# Task0301.net
KiCad netlist of a schematic drawn in Altium Designer
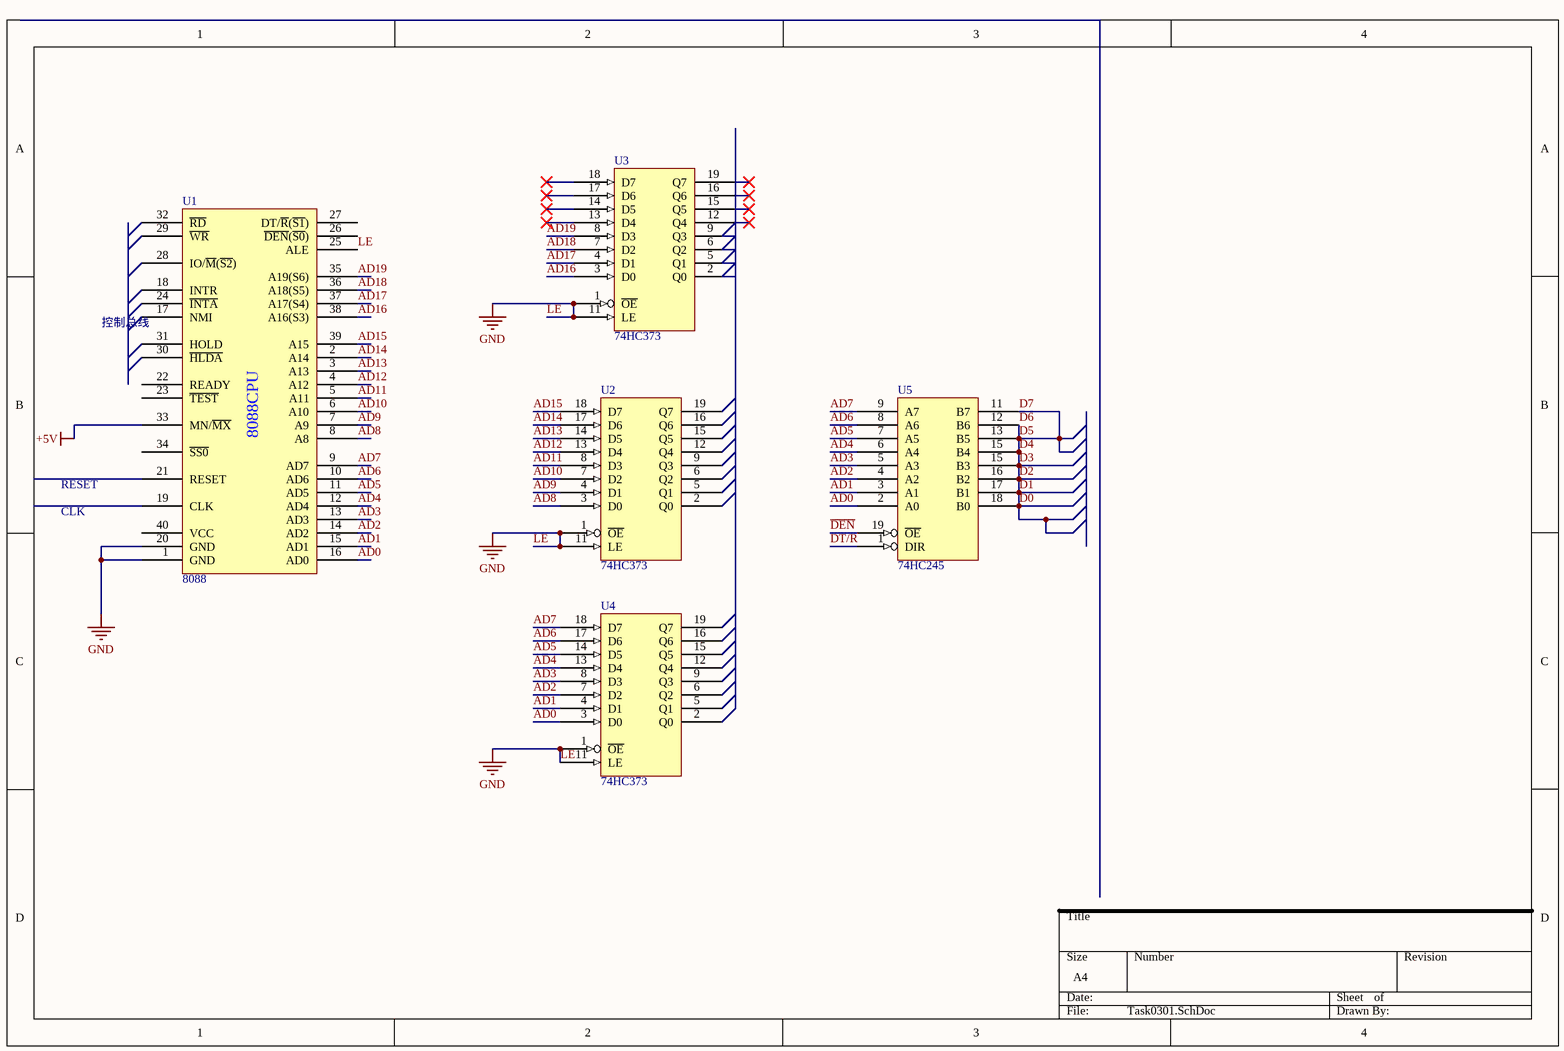
[diagram p0: Task0301.SchDoc]

(export (version "E")
  (design (tool "Eeschema 10.0.6"))
  (components
    (comp (ref "U1") (value "8088") (libsource (lib "8088ThreeBuses") (part "8088")))
    (comp (ref "U2") (value "74HC373") (libsource (lib "8088ThreeBuses") (part "74HC373")))
    (comp (ref "U3") (value "74HC373") (libsource (lib "8088ThreeBuses") (part "74HC373")))
    (comp (ref "U4") (value "74HC373") (libsource (lib "8088ThreeBuses") (part "74HC373")))
    (comp (ref "U5") (value "74HC245") (libsource (lib "8088ThreeBuses") (part "74HC245")))
  )
  (nets
    (net (code "1") (name "+5V") (class "Default")
      (node (ref "U1") (pin "33") (pinfunction "MN/~{MX}_33") (pintype "passive"))
    )
    (net (code "2") (name "/AD0") (class "Default")
      (node (ref "U1") (pin "16") (pinfunction "AD0_16") (pintype "passive"))
      (node (ref "U4") (pin "3") (pinfunction "D0_3") (pintype "input"))
      (node (ref "U5") (pin "2") (pinfunction "A0_2") (pintype "passive"))
    )
    (net (code "3") (name "/AD1") (class "Default")
      (node (ref "U1") (pin "15") (pinfunction "AD1_15") (pintype "passive"))
      (node (ref "U4") (pin "4") (pinfunction "D1_4") (pintype "input"))
      (node (ref "U5") (pin "3") (pinfunction "A1_3") (pintype "passive"))
    )
    (net (code "4") (name "/AD2") (class "Default")
      (node (ref "U1") (pin "14") (pinfunction "AD2_14") (pintype "passive"))
      (node (ref "U4") (pin "7") (pinfunction "D2_7") (pintype "input"))
      (node (ref "U5") (pin "4") (pinfunction "A2_4") (pintype "passive"))
    )
    (net (code "5") (name "/AD3") (class "Default")
      (node (ref "U1") (pin "13") (pinfunction "AD3_13") (pintype "passive"))
      (node (ref "U4") (pin "8") (pinfunction "D3_8") (pintype "input"))
      (node (ref "U5") (pin "5") (pinfunction "A3_5") (pintype "passive"))
    )
    (net (code "6") (name "/AD4") (class "Default")
      (node (ref "U1") (pin "12") (pinfunction "AD4_12") (pintype "passive"))
      (node (ref "U4") (pin "13") (pinfunction "D4_13") (pintype "input"))
      (node (ref "U5") (pin "6") (pinfunction "A4_6") (pintype "passive"))
    )
    (net (code "7") (name "/AD5") (class "Default")
      (node (ref "U1") (pin "11") (pinfunction "AD5_11") (pintype "passive"))
      (node (ref "U4") (pin "14") (pinfunction "D5_14") (pintype "input"))
      (node (ref "U5") (pin "7") (pinfunction "A5_7") (pintype "passive"))
    )
    (net (code "8") (name "/AD6") (class "Default")
      (node (ref "U1") (pin "10") (pinfunction "AD6_10") (pintype "passive"))
      (node (ref "U4") (pin "17") (pinfunction "D6_17") (pintype "input"))
      (node (ref "U5") (pin "8") (pinfunction "A6_8") (pintype "passive"))
    )
    (net (code "9") (name "/AD7") (class "Default")
      (node (ref "U1") (pin "9") (pinfunction "AD7_9") (pintype "passive"))
      (node (ref "U4") (pin "18") (pinfunction "D7_18") (pintype "input"))
      (node (ref "U5") (pin "9") (pinfunction "A7_9") (pintype "passive"))
    )
    (net (code "10") (name "/AD8") (class "Default")
      (node (ref "U1") (pin "8") (pinfunction "A8_8") (pintype "passive"))
      (node (ref "U2") (pin "3") (pinfunction "D0_3") (pintype "input"))
    )
    (net (code "11") (name "/AD9") (class "Default")
      (node (ref "U1") (pin "7") (pinfunction "A9_7") (pintype "passive"))
      (node (ref "U2") (pin "4") (pinfunction "D1_4") (pintype "input"))
    )
    (net (code "12") (name "/AD10") (class "Default")
      (node (ref "U1") (pin "6") (pinfunction "A10_6") (pintype "passive"))
      (node (ref "U2") (pin "7") (pinfunction "D2_7") (pintype "input"))
    )
    (net (code "13") (name "/AD11") (class "Default")
      (node (ref "U1") (pin "5") (pinfunction "A11_5") (pintype "passive"))
      (node (ref "U2") (pin "8") (pinfunction "D3_8") (pintype "input"))
    )
    (net (code "14") (name "/AD12") (class "Default")
      (node (ref "U1") (pin "4") (pinfunction "A12_4") (pintype "passive"))
      (node (ref "U2") (pin "13") (pinfunction "D4_13") (pintype "input"))
    )
    (net (code "15") (name "/AD13") (class "Default")
      (node (ref "U1") (pin "3") (pinfunction "A13_3") (pintype "passive"))
      (node (ref "U2") (pin "14") (pinfunction "D5_14") (pintype "input"))
    )
    (net (code "16") (name "/AD14") (class "Default")
      (node (ref "U1") (pin "2") (pinfunction "A14_2") (pintype "passive"))
      (node (ref "U2") (pin "17") (pinfunction "D6_17") (pintype "input"))
    )
    (net (code "17") (name "/AD15") (class "Default")
      (node (ref "U1") (pin "39") (pinfunction "A15_39") (pintype "passive"))
      (node (ref "U2") (pin "18") (pinfunction "D7_18") (pintype "input"))
    )
    (net (code "18") (name "/AD16") (class "Default")
      (node (ref "U1") (pin "38") (pinfunction "A16(S3)_38") (pintype "passive"))
      (node (ref "U3") (pin "3") (pinfunction "D0_3") (pintype "input"))
    )
    (net (code "19") (name "/AD17") (class "Default")
      (node (ref "U1") (pin "37") (pinfunction "A17(S4)_37") (pintype "passive"))
      (node (ref "U3") (pin "4") (pinfunction "D1_4") (pintype "input"))
    )
    (net (code "20") (name "/AD18") (class "Default")
      (node (ref "U1") (pin "36") (pinfunction "A18(S5)_36") (pintype "passive"))
      (node (ref "U3") (pin "7") (pinfunction "D2_7") (pintype "input"))
    )
    (net (code "21") (name "/AD19") (class "Default")
      (node (ref "U1") (pin "35") (pinfunction "A19(S6)_35") (pintype "passive"))
      (node (ref "U3") (pin "8") (pinfunction "D3_8") (pintype "input"))
    )
    (net (code "22") (name "/D0") (class "Default")
      (node (ref "U5") (pin "11") (pinfunction "B7_11") (pintype "tri_state"))
      (node (ref "U5") (pin "12") (pinfunction "B6_12") (pintype "tri_state"))
      (node (ref "U5") (pin "13") (pinfunction "B5_13") (pintype "tri_state"))
      (node (ref "U5") (pin "15") (pinfunction "B4_15") (pintype "tri_state"))
      (node (ref "U5") (pin "16") (pinfunction "B2_16") (pintype "tri_state"))
      (node (ref "U5") (pin "17") (pinfunction "B1_17") (pintype "tri_state"))
      (node (ref "U5") (pin "18") (pinfunction "B0_18") (pintype "tri_state"))
    )
    (net (code "23") (name "/DT{slash}~{R}") (class "Default")
      (node (ref "U5") (pin "1") (pinfunction "DIR_1") (pintype "input"))
    )
    (net (code "24") (name "/~{DEN}") (class "Default")
      (node (ref "U5") (pin "19") (pinfunction "~{OE}_19") (pintype "input"))
    )
    (net (code "25") (name "GND") (class "Default")
      (node (ref "U1") (pin "1") (pinfunction "GND_1") (pintype "passive"))
      (node (ref "U1") (pin "20") (pinfunction "GND_20") (pintype "passive"))
      (node (ref "U1") (pin "25") (pinfunction "ALE_25") (pintype "passive"))
      (node (ref "U2") (pin "1") (pinfunction "~{OE}_1") (pintype "input"))
      (node (ref "U2") (pin "11") (pinfunction "LE_11") (pintype "input"))
      (node (ref "U3") (pin "1") (pinfunction "~{OE}_1") (pintype "input"))
      (node (ref "U3") (pin "11") (pinfunction "LE_11") (pintype "input"))
      (node (ref "U4") (pin "1") (pinfunction "~{OE}_1") (pintype "input"))
      (node (ref "U4") (pin "11") (pinfunction "LE_11") (pintype "input"))
    )
    (net (code "26") (name "unconnected-(U1-CLK-Pad19)") (class "Default")
      (node (ref "U1") (pin "19") (pinfunction "CLK_19") (pintype "passive"))
    )
    (net (code "27") (name "unconnected-(U1-DT{slash}~{R}(~{S1})-Pad27)") (class "Default")
      (node (ref "U1") (pin "27") (pinfunction "DT/~{R}(~{S1})_27") (pintype "passive"))
    )
    (net (code "28") (name "unconnected-(U1-HOLD-Pad31)") (class "Default")
      (node (ref "U1") (pin "31") (pinfunction "HOLD_31") (pintype "passive"))
    )
    (net (code "29") (name "unconnected-(U1-INTR-Pad18)") (class "Default")
      (node (ref "U1") (pin "18") (pinfunction "INTR_18") (pintype "passive"))
    )
    (net (code "30") (name "unconnected-(U1-IO{slash}~{M}(~{S2})-Pad28)") (class "Default")
      (node (ref "U1") (pin "28") (pinfunction "IO/~{M}(~{S2})_28") (pintype "passive"))
    )
    (net (code "31") (name "unconnected-(U1-NMI-Pad17)") (class "Default")
      (node (ref "U1") (pin "17") (pinfunction "NMI_17") (pintype "passive"))
    )
    (net (code "32") (name "unconnected-(U1-READY-Pad22)") (class "Default")
      (node (ref "U1") (pin "22") (pinfunction "READY_22") (pintype "passive"))
    )
    (net (code "33") (name "unconnected-(U1-RESET-Pad21)") (class "Default")
      (node (ref "U1") (pin "21") (pinfunction "RESET_21") (pintype "passive"))
    )
    (net (code "34") (name "unconnected-(U1-VCC-Pad40)") (class "Default")
      (node (ref "U1") (pin "40") (pinfunction "VCC_40") (pintype "passive"))
    )
    (net (code "35") (name "unconnected-(U1-~{DEN}(~{S0})-Pad26)") (class "Default")
      (node (ref "U1") (pin "26") (pinfunction "~{DEN}(~{S0})_26") (pintype "passive"))
    )
    (net (code "36") (name "unconnected-(U1-~{HLDA}-Pad30)") (class "Default")
      (node (ref "U1") (pin "30") (pinfunction "~{HLDA}_30") (pintype "passive"))
    )
    (net (code "37") (name "unconnected-(U1-~{INTA}-Pad24)") (class "Default")
      (node (ref "U1") (pin "24") (pinfunction "~{INTA}_24") (pintype "passive"))
    )
    (net (code "38") (name "unconnected-(U1-~{RD}-Pad32)") (class "Default")
      (node (ref "U1") (pin "32") (pinfunction "~{RD}_32") (pintype "passive"))
    )
    (net (code "39") (name "unconnected-(U1-~{SS0}-Pad34)") (class "Default")
      (node (ref "U1") (pin "34") (pinfunction "~{SS0}_34") (pintype "passive"))
    )
    (net (code "40") (name "unconnected-(U1-~{TEST}-Pad23)") (class "Default")
      (node (ref "U1") (pin "23") (pinfunction "~{TEST}_23") (pintype "passive"))
    )
    (net (code "41") (name "unconnected-(U1-~{WR}-Pad29)") (class "Default")
      (node (ref "U1") (pin "29") (pinfunction "~{WR}_29") (pintype "passive"))
    )
    (net (code "42") (name "unconnected-(U2-Q0-Pad2)") (class "Default")
      (node (ref "U2") (pin "2") (pinfunction "Q0_2") (pintype "tri_state"))
    )
    (net (code "43") (name "unconnected-(U2-Q1-Pad5)") (class "Default")
      (node (ref "U2") (pin "5") (pinfunction "Q1_5") (pintype "tri_state"))
    )
    (net (code "44") (name "unconnected-(U2-Q2-Pad6)") (class "Default")
      (node (ref "U2") (pin "6") (pinfunction "Q2_6") (pintype "tri_state"))
    )
    (net (code "45") (name "unconnected-(U2-Q3-Pad9)") (class "Default")
      (node (ref "U2") (pin "9") (pinfunction "Q3_9") (pintype "tri_state"))
    )
    (net (code "46") (name "unconnected-(U2-Q4-Pad12)") (class "Default")
      (node (ref "U2") (pin "12") (pinfunction "Q4_12") (pintype "tri_state"))
    )
    (net (code "47") (name "unconnected-(U2-Q5-Pad15)") (class "Default")
      (node (ref "U2") (pin "15") (pinfunction "Q5_15") (pintype "tri_state"))
    )
    (net (code "48") (name "unconnected-(U2-Q6-Pad16)") (class "Default")
      (node (ref "U2") (pin "16") (pinfunction "Q6_16") (pintype "tri_state"))
    )
    (net (code "49") (name "unconnected-(U2-Q7-Pad19)") (class "Default")
      (node (ref "U2") (pin "19") (pinfunction "Q7_19") (pintype "tri_state"))
    )
    (net (code "50") (name "unconnected-(U3-D4-Pad13)") (class "Default")
      (node (ref "U3") (pin "13") (pinfunction "D4_13") (pintype "input+no_connect"))
    )
    (net (code "51") (name "unconnected-(U3-D5-Pad14)") (class "Default")
      (node (ref "U3") (pin "14") (pinfunction "D5_14") (pintype "input+no_connect"))
    )
    (net (code "52") (name "unconnected-(U3-D6-Pad17)") (class "Default")
      (node (ref "U3") (pin "17") (pinfunction "D6_17") (pintype "input+no_connect"))
    )
    (net (code "53") (name "unconnected-(U3-D7-Pad18)") (class "Default")
      (node (ref "U3") (pin "18") (pinfunction "D7_18") (pintype "input+no_connect"))
    )
    (net (code "54") (name "unconnected-(U3-Q0-Pad2)") (class "Default")
      (node (ref "U3") (pin "2") (pinfunction "Q0_2") (pintype "tri_state"))
    )
    (net (code "55") (name "unconnected-(U3-Q1-Pad5)") (class "Default")
      (node (ref "U3") (pin "5") (pinfunction "Q1_5") (pintype "tri_state"))
    )
    (net (code "56") (name "unconnected-(U3-Q2-Pad6)") (class "Default")
      (node (ref "U3") (pin "6") (pinfunction "Q2_6") (pintype "tri_state"))
    )
    (net (code "57") (name "unconnected-(U3-Q3-Pad9)") (class "Default")
      (node (ref "U3") (pin "9") (pinfunction "Q3_9") (pintype "tri_state"))
    )
    (net (code "58") (name "unconnected-(U3-Q4-Pad12)") (class "Default")
      (node (ref "U3") (pin "12") (pinfunction "Q4_12") (pintype "tri_state+no_connect"))
    )
    (net (code "59") (name "unconnected-(U3-Q5-Pad15)") (class "Default")
      (node (ref "U3") (pin "15") (pinfunction "Q5_15") (pintype "tri_state+no_connect"))
    )
    (net (code "60") (name "unconnected-(U3-Q6-Pad16)") (class "Default")
      (node (ref "U3") (pin "16") (pinfunction "Q6_16") (pintype "tri_state+no_connect"))
    )
    (net (code "61") (name "unconnected-(U3-Q7-Pad19)") (class "Default")
      (node (ref "U3") (pin "19") (pinfunction "Q7_19") (pintype "tri_state+no_connect"))
    )
    (net (code "62") (name "unconnected-(U4-Q0-Pad2)") (class "Default")
      (node (ref "U4") (pin "2") (pinfunction "Q0_2") (pintype "tri_state"))
    )
    (net (code "63") (name "unconnected-(U4-Q1-Pad5)") (class "Default")
      (node (ref "U4") (pin "5") (pinfunction "Q1_5") (pintype "tri_state"))
    )
    (net (code "64") (name "unconnected-(U4-Q2-Pad6)") (class "Default")
      (node (ref "U4") (pin "6") (pinfunction "Q2_6") (pintype "tri_state"))
    )
    (net (code "65") (name "unconnected-(U4-Q3-Pad9)") (class "Default")
      (node (ref "U4") (pin "9") (pinfunction "Q3_9") (pintype "tri_state"))
    )
    (net (code "66") (name "unconnected-(U4-Q4-Pad12)") (class "Default")
      (node (ref "U4") (pin "12") (pinfunction "Q4_12") (pintype "tri_state"))
    )
    (net (code "67") (name "unconnected-(U4-Q5-Pad15)") (class "Default")
      (node (ref "U4") (pin "15") (pinfunction "Q5_15") (pintype "tri_state"))
    )
    (net (code "68") (name "unconnected-(U4-Q6-Pad16)") (class "Default")
      (node (ref "U4") (pin "16") (pinfunction "Q6_16") (pintype "tri_state"))
    )
    (net (code "69") (name "unconnected-(U4-Q7-Pad19)") (class "Default")
      (node (ref "U4") (pin "19") (pinfunction "Q7_19") (pintype "tri_state"))
    )
  )
)
